# Kodi_Remote.net
KiCad netlist of a schematic drawn in EAGLE
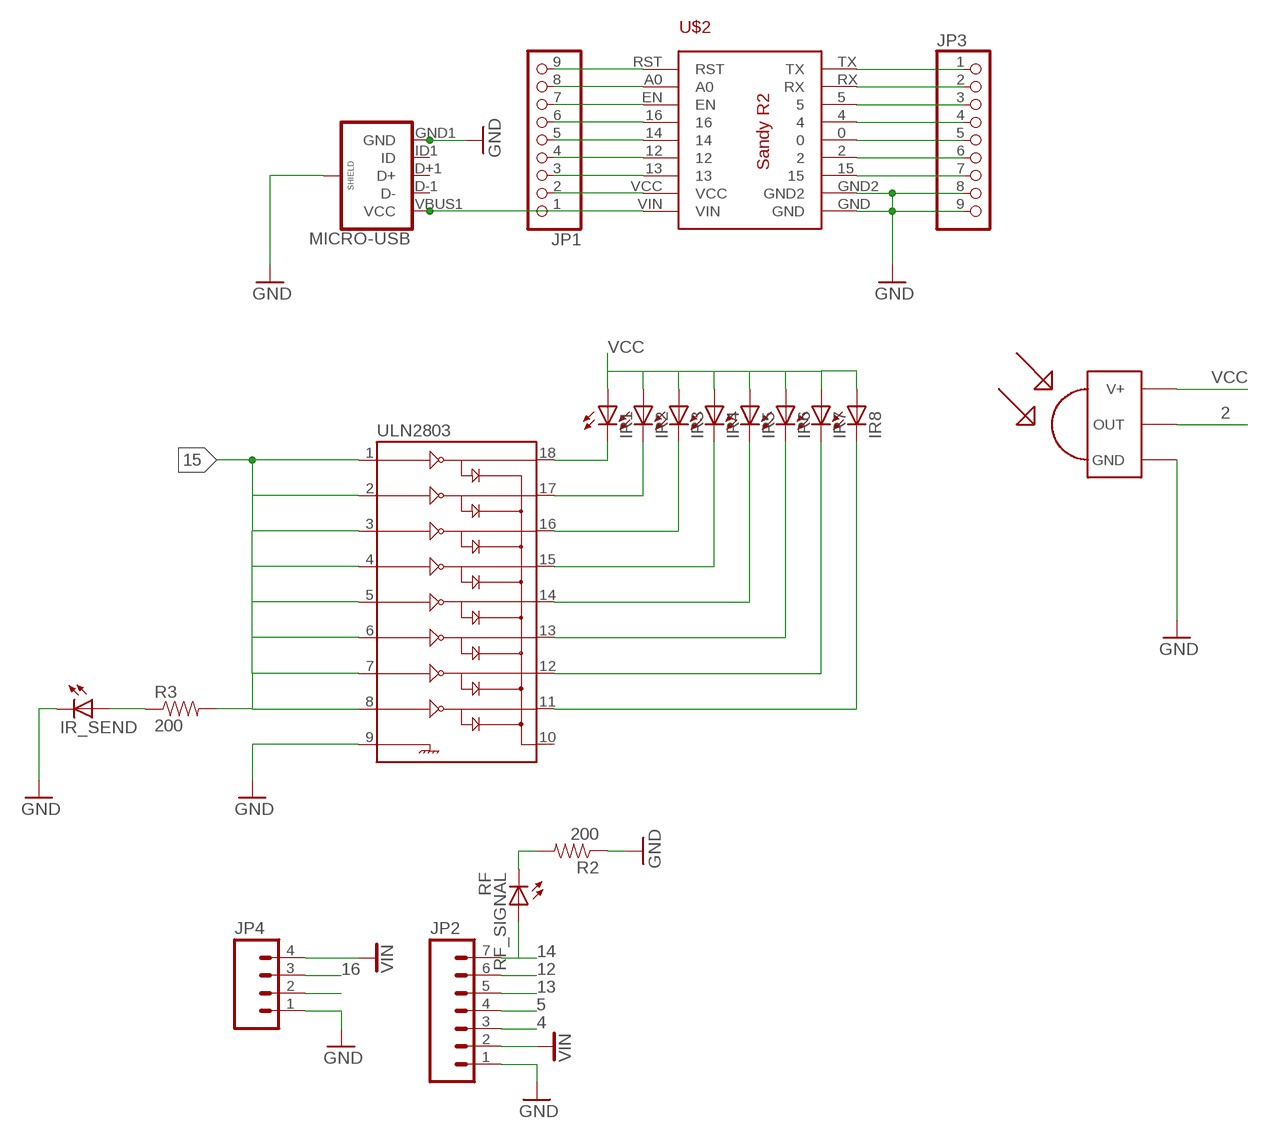
[diagram p0: schematic, sheet 1]

(export (version "E")
  (design (tool "Eeschema 10.0.6"))
  (components
    (comp (ref "IR1")
      (value "LED5MM")
      (footprint "eagle-import:LED5MM")
      (libsource (lib "eagle-import") (part "LED5MM"))
    )
    (comp (ref "IR2")
      (value "LED5MM")
      (footprint "eagle-import:LED5MM")
      (libsource (lib "eagle-import") (part "LED5MM"))
    )
    (comp (ref "IR3")
      (value "LED5MM")
      (footprint "eagle-import:LED5MM")
      (libsource (lib "eagle-import") (part "LED5MM"))
    )
    (comp (ref "IR4")
      (value "LED5MM")
      (footprint "eagle-import:LED5MM")
      (libsource (lib "eagle-import") (part "LED5MM"))
    )
    (comp (ref "IR5")
      (value "LED5MM")
      (footprint "eagle-import:LED5MM")
      (libsource (lib "eagle-import") (part "LED5MM"))
    )
    (comp (ref "IR6")
      (value "LED5MM")
      (footprint "eagle-import:LED5MM")
      (libsource (lib "eagle-import") (part "LED5MM"))
    )
    (comp (ref "IR7")
      (value "LED5MM")
      (footprint "eagle-import:LED5MM")
      (libsource (lib "eagle-import") (part "LED5MM"))
    )
    (comp (ref "IR8")
      (value "LED5MM")
      (footprint "eagle-import:LED5MM")
      (libsource (lib "eagle-import") (part "LED5MM"))
    )
    (comp (ref "IR_SEND")
      (value "LED3MM")
      (footprint "eagle-import:LED3MM")
      (libsource (lib "eagle-import") (part "LED3MM"))
    )
    (comp (ref "JP1")
      (value "PINHD-1X9")
      (footprint "eagle-import:1X09-BIG")
      (libsource (lib "eagle-import") (part "PINHD-1X9"))
    )
    (comp (ref "JP2")
      (value "M07")
      (footprint "eagle-import:1X07")
      (libsource (lib "eagle-import") (part "M07"))
    )
    (comp (ref "JP3")
      (value "PINHD-1X9")
      (footprint "eagle-import:1X09-BIG")
      (libsource (lib "eagle-import") (part "PINHD-1X9"))
    )
    (comp (ref "JP4")
      (value "M04PTH")
      (footprint "eagle-import:1X04")
      (libsource (lib "eagle-import") (part "M04PTH"))
    )
    (comp (ref "MICRO-USB")
      (value "USB_MICROB_PLUGCONN-11752")
      (footprint "eagle-import:USB-B-MICRO-SMD_V03")
      (libsource (lib "eagle-import") (part "USB_MICROB_PLUGCONN-11752"))
    )
    (comp (ref "R2")
      (value "200")
      (footprint "eagle-import:0805")
      (libsource (lib "eagle-import") (part "RESISTOR0805-RES"))
    )
    (comp (ref "R3")
      (value "200")
      (footprint "eagle-import:0805")
      (libsource (lib "eagle-import") (part "RESISTOR0805-RES"))
    )
    (comp (ref "RF_SIGNAL")
      (value "RF")
      (footprint "eagle-import:LED3MM")
      (libsource (lib "eagle-import") (part "LED3MM"))
    )
    (comp (ref "TSOP1838")
      (value "TSOP1838")
      (footprint "eagle-import:TSOP18XX")
      (libsource (lib "eagle-import") (part "TSOP1838"))
    )
    (comp (ref "U$2")
      (value "MINI-ESPMINI-ESP-LOCK")
      (footprint "eagle-import:MINI-ESP-LOCK")
      (libsource (lib "eagle-import") (part "MINI-ESPMINI-ESP-LOCK"))
    )
    (comp (ref "ULN2803")
      (value "ULN2803DIP")
      (footprint "eagle-import:DIL18")
      (libsource (lib "eagle-import") (part "ULN2803DIP"))
    )
  )
  (nets
    (net (code "1") (name "/2") (class "Default")
      (node (ref "JP3") (pin "6") (pinfunction "6_6") (pintype "passive"))
      (node (ref "TSOP1838") (pin "OUT") (pinfunction "OUT_OUT") (pintype "bidirectional"))
      (node (ref "U$2") (pin "2") (pinfunction "2_2") (pintype "bidirectional"))
    )
    (net (code "2") (name "/4") (class "Default")
      (node (ref "JP2") (pin "3") (pinfunction "3_3") (pintype "passive"))
      (node (ref "JP3") (pin "4") (pinfunction "4_4") (pintype "passive"))
      (node (ref "U$2") (pin "4") (pinfunction "4_4") (pintype "bidirectional"))
    )
    (net (code "3") (name "/5") (class "Default")
      (node (ref "JP2") (pin "4") (pinfunction "4_4") (pintype "passive"))
      (node (ref "JP3") (pin "3") (pinfunction "3_3") (pintype "passive"))
      (node (ref "U$2") (pin "5") (pinfunction "5_5") (pintype "bidirectional"))
    )
    (net (code "4") (name "/12") (class "Default")
      (node (ref "JP1") (pin "4") (pinfunction "4_4") (pintype "passive"))
      (node (ref "JP2") (pin "6") (pinfunction "6_6") (pintype "passive"))
      (node (ref "U$2") (pin "12") (pinfunction "12_12") (pintype "bidirectional"))
    )
    (net (code "5") (name "/13") (class "Default")
      (node (ref "JP1") (pin "3") (pinfunction "3_3") (pintype "passive"))
      (node (ref "JP2") (pin "5") (pinfunction "5_5") (pintype "passive"))
      (node (ref "U$2") (pin "13") (pinfunction "13_13") (pintype "bidirectional"))
    )
    (net (code "6") (name "/14") (class "Default")
      (node (ref "JP1") (pin "5") (pinfunction "5_5") (pintype "passive"))
      (node (ref "JP2") (pin "7") (pinfunction "7_7") (pintype "passive"))
      (node (ref "RF_SIGNAL") (pin "A") (pinfunction "A_A") (pintype "passive"))
      (node (ref "U$2") (pin "14") (pinfunction "14_14") (pintype "bidirectional"))
    )
    (net (code "7") (name "/16") (class "Default")
      (node (ref "JP1") (pin "6") (pinfunction "6_6") (pintype "passive"))
      (node (ref "JP4") (pin "3") (pinfunction "3_3") (pintype "passive"))
      (node (ref "U$2") (pin "16") (pinfunction "16_16") (pintype "bidirectional"))
    )
    (net (code "8") (name "/VCC") (class "Default")
      (node (ref "IR1") (pin "A") (pinfunction "A_A") (pintype "passive"))
      (node (ref "IR2") (pin "A") (pinfunction "A_A") (pintype "passive"))
      (node (ref "IR3") (pin "A") (pinfunction "A_A") (pintype "passive"))
      (node (ref "IR4") (pin "A") (pinfunction "A_A") (pintype "passive"))
      (node (ref "IR5") (pin "A") (pinfunction "A_A") (pintype "passive"))
      (node (ref "IR6") (pin "A") (pinfunction "A_A") (pintype "passive"))
      (node (ref "IR7") (pin "A") (pinfunction "A_A") (pintype "passive"))
      (node (ref "IR8") (pin "A") (pinfunction "A_A") (pintype "passive"))
      (node (ref "JP1") (pin "2") (pinfunction "2_2") (pintype "passive"))
      (node (ref "TSOP1838") (pin "VCC") (pinfunction "V+_VCC") (pintype "bidirectional"))
      (node (ref "U$2") (pin "VCC") (pinfunction "VCC_VCC") (pintype "bidirectional"))
    )
    (net (code "9") (name "15") (class "Default")
      (node (ref "JP3") (pin "7") (pinfunction "7_7") (pintype "passive"))
      (node (ref "R3") (pin "2") (pinfunction "2_2") (pintype "passive"))
      (node (ref "U$2") (pin "15") (pinfunction "15_15") (pintype "bidirectional"))
      (node (ref "ULN2803") (pin "1") (pinfunction "1_1") (pintype "bidirectional"))
      (node (ref "ULN2803") (pin "2") (pinfunction "2_2") (pintype "bidirectional"))
      (node (ref "ULN2803") (pin "3") (pinfunction "3_3") (pintype "bidirectional"))
      (node (ref "ULN2803") (pin "4") (pinfunction "4_4") (pintype "bidirectional"))
      (node (ref "ULN2803") (pin "5") (pinfunction "5_5") (pintype "bidirectional"))
      (node (ref "ULN2803") (pin "6") (pinfunction "6_6") (pintype "bidirectional"))
      (node (ref "ULN2803") (pin "7") (pinfunction "7_7") (pintype "bidirectional"))
      (node (ref "ULN2803") (pin "8") (pinfunction "8_8") (pintype "bidirectional"))
    )
    (net (code "10") (name "GND") (class "Default")
      (node (ref "IR_SEND") (pin "K") (pinfunction "C_K") (pintype "passive"))
      (node (ref "JP2") (pin "1") (pinfunction "1_1") (pintype "passive"))
      (node (ref "JP3") (pin "8") (pinfunction "8_8") (pintype "passive"))
      (node (ref "JP3") (pin "9") (pinfunction "9_9") (pintype "passive"))
      (node (ref "JP4") (pin "1") (pinfunction "1_1") (pintype "passive"))
      (node (ref "MICRO-USB") (pin "GND1") (pinfunction "GND_GND1") (pintype "bidirectional"))
      (node (ref "MICRO-USB") (pin "SHIELD1") (pinfunction "SHIELD_SHIELD1") (pintype "bidirectional"))
      (node (ref "MICRO-USB") (pin "SHIELD2") (pinfunction "SHIELD_SHIELD2") (pintype "bidirectional"))
      (node (ref "MICRO-USB") (pin "SHIELD3") (pinfunction "SHIELD_SHIELD3") (pintype "bidirectional"))
      (node (ref "R2") (pin "1") (pinfunction "1_1") (pintype "passive"))
      (node (ref "TSOP1838") (pin "GND") (pinfunction "GND_GND") (pintype "bidirectional"))
      (node (ref "U$2") (pin "GND") (pinfunction "GND_GND") (pintype "bidirectional"))
      (node (ref "U$2") (pin "GND2") (pinfunction "GND2_GND2") (pintype "bidirectional"))
      (node (ref "ULN2803") (pin "9") (pinfunction "9_9") (pintype "bidirectional"))
    )
    (net (code "11") (name "Net-(IR1-C)") (class "Default")
      (node (ref "IR1") (pin "K") (pinfunction "C_K") (pintype "passive"))
      (node (ref "ULN2803") (pin "18") (pinfunction "18_18") (pintype "bidirectional"))
    )
    (net (code "12") (name "Net-(IR2-C)") (class "Default")
      (node (ref "IR2") (pin "K") (pinfunction "C_K") (pintype "passive"))
      (node (ref "ULN2803") (pin "17") (pinfunction "17_17") (pintype "bidirectional"))
    )
    (net (code "13") (name "Net-(IR3-C)") (class "Default")
      (node (ref "IR3") (pin "K") (pinfunction "C_K") (pintype "passive"))
      (node (ref "ULN2803") (pin "16") (pinfunction "16_16") (pintype "bidirectional"))
    )
    (net (code "14") (name "Net-(IR4-C)") (class "Default")
      (node (ref "IR4") (pin "K") (pinfunction "C_K") (pintype "passive"))
      (node (ref "ULN2803") (pin "15") (pinfunction "15_15") (pintype "bidirectional"))
    )
    (net (code "15") (name "Net-(IR5-C)") (class "Default")
      (node (ref "IR5") (pin "K") (pinfunction "C_K") (pintype "passive"))
      (node (ref "ULN2803") (pin "14") (pinfunction "14_14") (pintype "bidirectional"))
    )
    (net (code "16") (name "Net-(IR6-C)") (class "Default")
      (node (ref "IR6") (pin "K") (pinfunction "C_K") (pintype "passive"))
      (node (ref "ULN2803") (pin "13") (pinfunction "13_13") (pintype "bidirectional"))
    )
    (net (code "17") (name "Net-(IR7-C)") (class "Default")
      (node (ref "IR7") (pin "K") (pinfunction "C_K") (pintype "passive"))
      (node (ref "ULN2803") (pin "12") (pinfunction "12_12") (pintype "bidirectional"))
    )
    (net (code "18") (name "Net-(IR8-C)") (class "Default")
      (node (ref "IR8") (pin "K") (pinfunction "C_K") (pintype "passive"))
      (node (ref "ULN2803") (pin "11") (pinfunction "11_11") (pintype "bidirectional"))
    )
    (net (code "19") (name "Net-(IR_SEND-PadA)") (class "Default")
      (node (ref "IR_SEND") (pin "A") (pinfunction "A_A") (pintype "passive"))
      (node (ref "R3") (pin "1") (pinfunction "1_1") (pintype "passive"))
    )
    (net (code "20") (name "Net-(JP1-Pad7)") (class "Default")
      (node (ref "JP1") (pin "7") (pinfunction "7_7") (pintype "passive"))
      (node (ref "U$2") (pin "EN") (pinfunction "EN_EN") (pintype "bidirectional"))
    )
    (net (code "21") (name "Net-(JP1-Pad8)") (class "Default")
      (node (ref "JP1") (pin "8") (pinfunction "8_8") (pintype "passive"))
      (node (ref "U$2") (pin "A0") (pinfunction "A0_A0") (pintype "bidirectional"))
    )
    (net (code "22") (name "Net-(JP1-Pad9)") (class "Default")
      (node (ref "JP1") (pin "9") (pinfunction "9_9") (pintype "passive"))
      (node (ref "U$2") (pin "RST") (pinfunction "RST_RST") (pintype "bidirectional"))
    )
    (net (code "23") (name "Net-(JP3-Pad1)") (class "Default")
      (node (ref "JP3") (pin "1") (pinfunction "1_1") (pintype "passive"))
      (node (ref "U$2") (pin "TX") (pinfunction "TX_TX") (pintype "bidirectional"))
    )
    (net (code "24") (name "Net-(JP3-Pad2)") (class "Default")
      (node (ref "JP3") (pin "2") (pinfunction "2_2") (pintype "passive"))
      (node (ref "U$2") (pin "RX") (pinfunction "RX_RX") (pintype "bidirectional"))
    )
    (net (code "25") (name "Net-(JP3-Pad5)") (class "Default")
      (node (ref "JP3") (pin "5") (pinfunction "5_5") (pintype "passive"))
      (node (ref "U$2") (pin "0") (pinfunction "0_0") (pintype "bidirectional"))
    )
    (net (code "26") (name "Net-(RF_SIGNAL-C)") (class "Default")
      (node (ref "R2") (pin "2") (pinfunction "2_2") (pintype "passive"))
      (node (ref "RF_SIGNAL") (pin "K") (pinfunction "C_K") (pintype "passive"))
    )
    (net (code "27") (name "VIN") (class "Default")
      (node (ref "JP1") (pin "1") (pinfunction "1_1") (pintype "passive"))
      (node (ref "JP2") (pin "2") (pinfunction "2_2") (pintype "passive"))
      (node (ref "JP4") (pin "4") (pinfunction "4_4") (pintype "passive"))
      (node (ref "MICRO-USB") (pin "VBUS1") (pinfunction "VCC_VBUS1") (pintype "bidirectional"))
      (node (ref "U$2") (pin "VIN") (pinfunction "VIN_VIN") (pintype "bidirectional"))
    )
    (net (code "28") (name "unconnected-(JP4-Pad2)") (class "Default")
      (node (ref "JP4") (pin "2") (pinfunction "2_2") (pintype "passive"))
    )
    (net (code "29") (name "unconnected-(MICRO-USB-D+-PadD+1)") (class "Default")
      (node (ref "MICRO-USB") (pin "D+1") (pinfunction "D+_D+1") (pintype "bidirectional"))
    )
    (net (code "30") (name "unconnected-(MICRO-USB-D--PadD-1)") (class "Default")
      (node (ref "MICRO-USB") (pin "D-1") (pinfunction "D-_D-1") (pintype "bidirectional"))
    )
    (net (code "31") (name "unconnected-(MICRO-USB-ID-PadID1)") (class "Default")
      (node (ref "MICRO-USB") (pin "ID1") (pinfunction "ID_ID1") (pintype "bidirectional"))
    )
    (net (code "32") (name "unconnected-(ULN2803-Pad10)") (class "Default")
      (node (ref "ULN2803") (pin "10") (pinfunction "10_10") (pintype "bidirectional"))
    )
  )
)
